# RGB_light_master.net
KiCad netlist of a schematic drawn in EasyEDA Pro
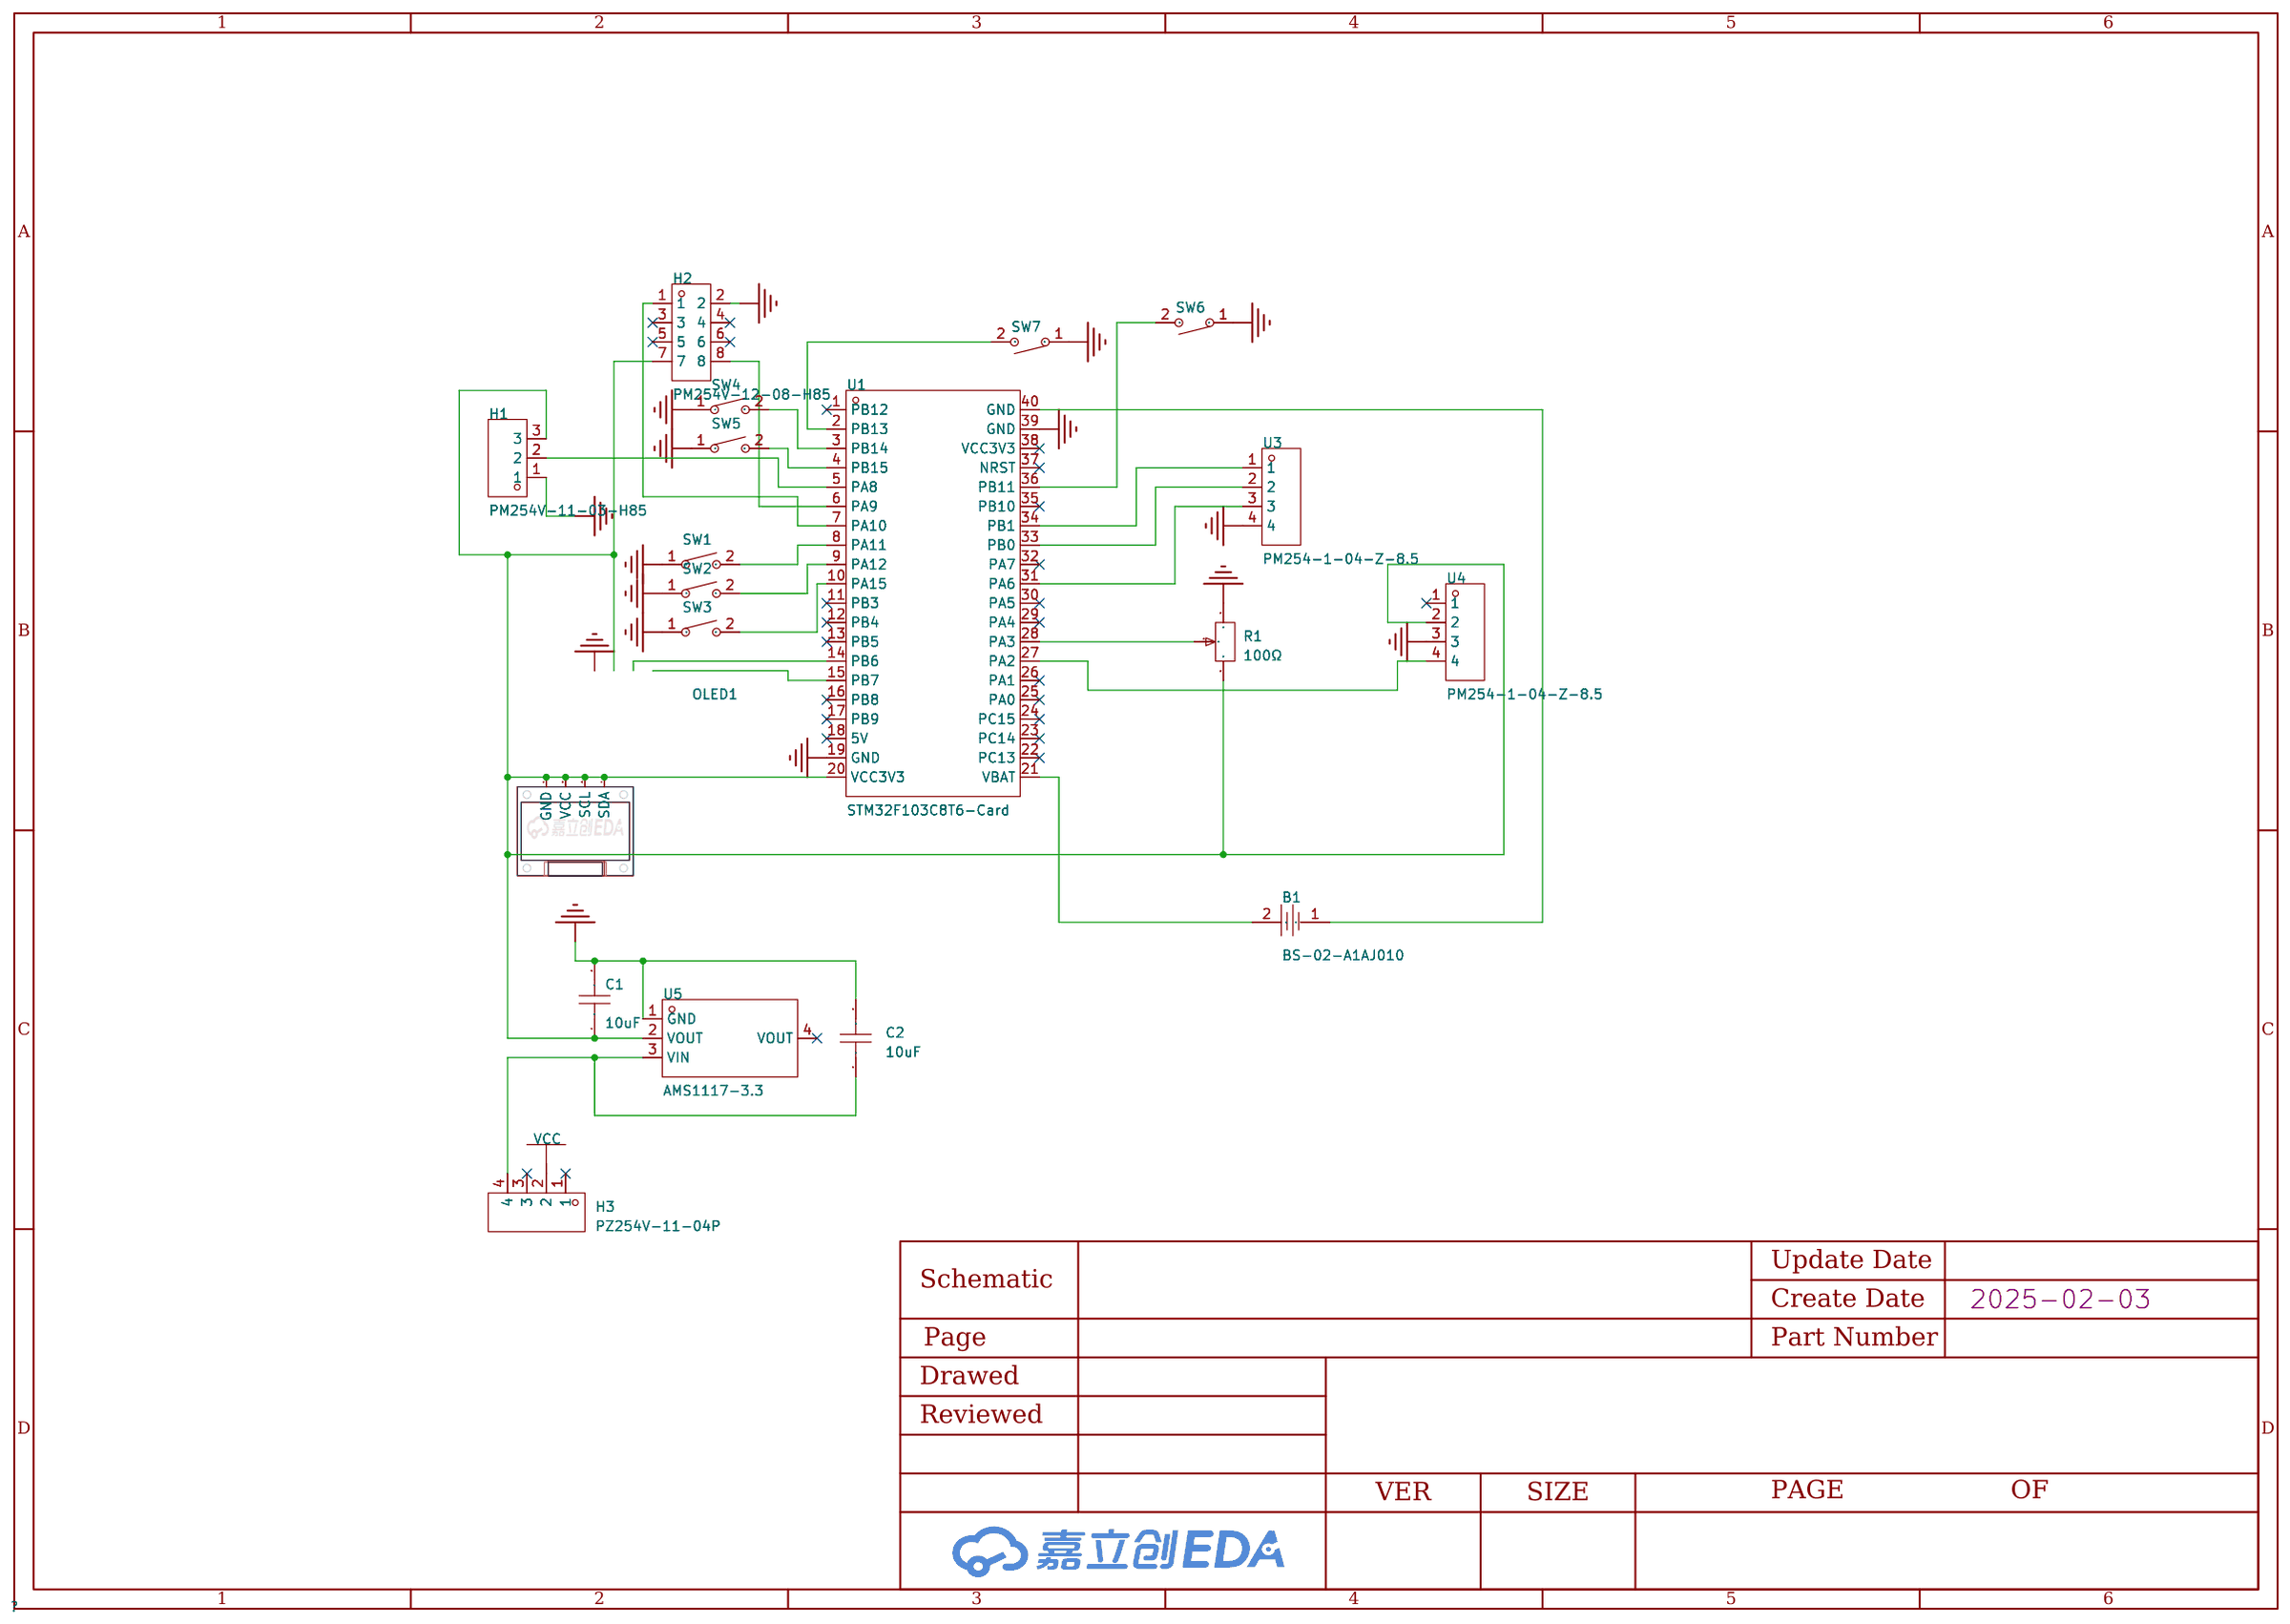
[diagram p0: schematic sheet]

(export (version "E")
  (design (tool "Eeschema 10.0.6"))
  (components
    (comp (ref "B1")
      (value "BS-02-A1AJ010")
      (footprint "easyedapro:BAT-TH_BS-02-A1AJ010")
      (description "连接器类型:电池底座;适用电池规格:CR2032;触头材质:磷青铜;触点电镀:镍;工作温度范围:-25°C~+85°C;")
      (fields (field (name "Manufacturer") "MYOUNG(美阳)"))
      (libsource (lib "easyedapro") (part "BS-02-A1AJ010"))
    )
    (comp (ref "C1")
      (value "10uF")
      (footprint "easyedapro:C0805")
      (description "容值:10uF;精度:±10%;额定电压:25V;材质(温度系数):X5R;")
      (fields
        (field (name "Manufacturer Part") "TMK212BBJ106KGHT")
        (field (name "Manufacturer") "TAIYO YUDEN(太诱)")
      )
      (libsource (lib "easyedapro") (part "TMK212BBJ106KGHT"))
    )
    (comp (ref "C2")
      (value "10uF")
      (footprint "easyedapro:C0805")
      (description "容值:10uF;精度:±10%;额定电压:25V;材质(温度系数):X5R;")
      (fields
        (field (name "Manufacturer Part") "TMK212BBJ106KGHT")
        (field (name "Manufacturer") "TAIYO YUDEN(太诱)")
      )
      (libsource (lib "easyedapro") (part "TMK212BBJ106KGHT"))
    )
    (comp (ref "H1")
      (value "PM254V-11-03-H85")
      (footprint "easyedapro:HDR-TH_3P-P2.54-V-F")
      (description "插孔结构:1x3P;间距:2.54mm;行距:-;安装类型:直插;排数:单排;总孔位数:3P;塑高:-;触头材质:黄铜;触头镀层:-;")
      (fields (field (name "Manufacturer") "XFCN(兴飞)"))
      (libsource (lib "easyedapro") (part "PM254V-11-03-H85"))
    )
    (comp (ref "H2")
      (value "PM254V-12-08-H85")
      (footprint "easyedapro:HDR-TH_8P-P2.54-V-F-R2-C4-S2.54")
      (fields (field (name "Manufacturer") "XFCN(兴飞)"))
      (libsource (lib "easyedapro") (part "PM254V-12-08-H85_C2834799"))
    )
    (comp (ref "H3")
      (value "PZ254V-11-04P")
      (footprint "easyedapro:HDR-TH_4P-P2.54-V-M")
      (fields (field (name "Manufacturer") "XFCN(兴飞)"))
      (libsource (lib "easyedapro") (part "PZ254V-11-04P_C2691448"))
    )
    (comp (ref "OLED1")
      (value "~")
      (footprint "easyedapro:0.96OLED_4P")
      (libsource (lib "easyedapro") (part "0.96OLED模块_4P"))
    )
    (comp (ref "R1")
      (value "100Ω")
      (footprint "easyedapro:RES-ADJ-TH_3296W")
      (description "阻值:100Ω;精度:±10%;")
      (fields (field (name "Manufacturer Part") "3296W-1-101LF") (field (name "Manufacturer") "BOURNS"))
      (libsource (lib "easyedapro") (part "3296W-1-101LF"))
    )
    (comp (ref "SW1")
      (value "TC-1101T-C-B-B")
      (footprint "easyedapro:KEY-TH_2P-L6.0-W3.5-P6.50")
      (fields (field (name "Manufacturer") "XKB Connectivity(中国星坤)"))
      (libsource (lib "easyedapro") (part "TC-1101T-C-B-B"))
    )
    (comp (ref "SW2")
      (value "TC-1101T-C-B-B")
      (footprint "easyedapro:KEY-TH_2P-L6.0-W3.5-P6.50")
      (fields (field (name "Manufacturer") "XKB Connectivity(中国星坤)"))
      (libsource (lib "easyedapro") (part "TC-1101T-C-B-B"))
    )
    (comp (ref "SW3")
      (value "TC-1101T-C-B-B")
      (footprint "easyedapro:KEY-TH_2P-L6.0-W3.5-P6.50")
      (fields (field (name "Manufacturer") "XKB Connectivity(中国星坤)"))
      (libsource (lib "easyedapro") (part "TC-1101T-C-B-B"))
    )
    (comp (ref "SW4")
      (value "TC-1101T-C-B-B")
      (footprint "easyedapro:KEY-TH_2P-L6.0-W3.5-P6.50")
      (fields (field (name "Manufacturer") "XKB Connectivity(中国星坤)"))
      (libsource (lib "easyedapro") (part "TC-1101T-C-B-B"))
    )
    (comp (ref "SW5")
      (value "TC-1101T-C-B-B")
      (footprint "easyedapro:KEY-TH_2P-L6.0-W3.5-P6.50")
      (fields (field (name "Manufacturer") "XKB Connectivity(中国星坤)"))
      (libsource (lib "easyedapro") (part "TC-1101T-C-B-B"))
    )
    (comp (ref "SW6")
      (value "TC-1101T-C-B-B")
      (footprint "easyedapro:KEY-TH_2P-L6.0-W3.5-P6.50")
      (fields (field (name "Manufacturer") "XKB Connectivity(中国星坤)"))
      (libsource (lib "easyedapro") (part "TC-1101T-C-B-B"))
    )
    (comp (ref "SW7")
      (value "TC-1101T-C-B-B")
      (footprint "easyedapro:KEY-TH_2P-L6.0-W3.5-P6.50")
      (fields (field (name "Manufacturer") "XKB Connectivity(中国星坤)"))
      (libsource (lib "easyedapro") (part "TC-1101T-C-B-B"))
    )
    (comp (ref "U1")
      (value "STM32F103C8T6-Card")
      (footprint "easyedapro:CONN-TH_L53.3-W22.9_STM32F103C8T6-CARD")
      (libsource (lib "easyedapro") (part "STM32F103C8T6-CARD"))
    )
    (comp (ref "U3")
      (value "PM254-1-04-Z-8.5")
      (footprint "easyedapro:hdr-th_4p-p2.54-v-f")
      (fields (field (name "Manufacturer") "HCTL(华灿天禄)"))
      (libsource (lib "easyedapro") (part "PM254-1-04-Z-8.5"))
    )
    (comp (ref "U4")
      (value "PM254-1-04-Z-8.5")
      (footprint "easyedapro:hdr-th_4p-p2.54-v-f")
      (fields (field (name "Manufacturer") "HCTL(华灿天禄)"))
      (libsource (lib "easyedapro") (part "PM254-1-04-Z-8.5"))
    )
    (comp (ref "U5")
      (value "AMS1117-3.3")
      (footprint "easyedapro:SOT-223-3_L6.5-W3.4-P2.30-LS7.0-BR")
      (description "输出类型:固定;最大输入电压:-;输出电压:3.3V;最大输出电流:1A;电源纹波抑制比(PSRR):72dB@(120Hz);输出极性:正极;")
      (fields (field (name "Manufacturer") "AMS"))
      (libsource (lib "easyedapro") (part "AMS1117-3.3"))
    )
  )
  (nets
    (net (code "1") (name "GND") (class "Default")
      (node (ref "C1") (pin "2") (pinfunction "2_2") (pintype "input"))
      (node (ref "C2") (pin "2") (pinfunction "2_2") (pintype "input"))
      (node (ref "H1") (pin "1") (pinfunction "1_1") (pintype "unspecified"))
      (node (ref "H2") (pin "2") (pinfunction "2_2") (pintype "unspecified"))
      (node (ref "R1") (pin "1") (pinfunction "1_1") (pintype "input"))
      (node (ref "SW1") (pin "1") (pinfunction "1_1") (pintype "unspecified"))
      (node (ref "SW2") (pin "1") (pinfunction "1_1") (pintype "unspecified"))
      (node (ref "SW3") (pin "1") (pinfunction "1_1") (pintype "unspecified"))
      (node (ref "SW4") (pin "1") (pinfunction "1_1") (pintype "unspecified"))
      (node (ref "SW5") (pin "1") (pinfunction "1_1") (pintype "unspecified"))
      (node (ref "SW6") (pin "1") (pinfunction "1_1") (pintype "unspecified"))
      (node (ref "SW7") (pin "1") (pinfunction "1_1") (pintype "unspecified"))
      (node (ref "U1") (pin "19") (pinfunction "GND_19") (pintype "unspecified"))
      (node (ref "U1") (pin "39") (pinfunction "GND_39") (pintype "unspecified"))
      (node (ref "U3") (pin "4") (pinfunction "4_4") (pintype "unspecified"))
      (node (ref "U4") (pin "3") (pinfunction "3_3") (pintype "unspecified"))
      (node (ref "U5") (pin "1") (pinfunction "GND_1") (pintype "unspecified"))
    )
    (net (code "2") (name "Net-(B1-Pad1)") (class "Default")
      (node (ref "B1") (pin "1") (pinfunction "1_1") (pintype "input"))
      (node (ref "U1") (pin "40") (pinfunction "GND_40") (pintype "unspecified"))
    )
    (net (code "3") (name "Net-(OLED1-GND)") (class "Default")
      (node (ref "C1") (pin "1") (pinfunction "1_1") (pintype "input"))
      (node (ref "H1") (pin "3") (pinfunction "3_3") (pintype "unspecified"))
      (node (ref "H2") (pin "7") (pinfunction "7_7") (pintype "unspecified"))
      (node (ref "OLED1") (pin "1") (pinfunction "GND_1") (pintype "input"))
      (node (ref "OLED1") (pin "2") (pinfunction "VCC_2") (pintype "input"))
      (node (ref "OLED1") (pin "3") (pinfunction "SCL_3") (pintype "input"))
      (node (ref "OLED1") (pin "4") (pinfunction "SDA_4") (pintype "input"))
      (node (ref "R1") (pin "3") (pinfunction "3_3") (pintype "input"))
      (node (ref "U1") (pin "20") (pinfunction "VCC3V3_20") (pintype "unspecified"))
      (node (ref "U4") (pin "2") (pinfunction "2_2") (pintype "unspecified"))
      (node (ref "U5") (pin "2") (pinfunction "VOUT_2") (pintype "unspecified"))
    )
    (net (code "4") (name "Net-(U1-PA2)") (class "Default")
      (node (ref "U1") (pin "27") (pinfunction "PA2_27") (pintype "unspecified"))
      (node (ref "U4") (pin "4") (pinfunction "4_4") (pintype "unspecified"))
    )
    (net (code "5") (name "Net-(U1-PA3)") (class "Default")
      (node (ref "R1") (pin "2") (pinfunction "2_2") (pintype "input"))
      (node (ref "U1") (pin "28") (pinfunction "PA3_28") (pintype "unspecified"))
    )
    (net (code "6") (name "Net-(U1-PA6)") (class "Default")
      (node (ref "U1") (pin "31") (pinfunction "PA6_31") (pintype "unspecified"))
      (node (ref "U3") (pin "3") (pinfunction "3_3") (pintype "unspecified"))
    )
    (net (code "7") (name "Net-(U1-PA8)") (class "Default")
      (node (ref "H1") (pin "2") (pinfunction "2_2") (pintype "unspecified"))
      (node (ref "U1") (pin "5") (pinfunction "PA8_5") (pintype "unspecified"))
    )
    (net (code "8") (name "Net-(U1-PA9)") (class "Default")
      (node (ref "H2") (pin "8") (pinfunction "8_8") (pintype "unspecified"))
      (node (ref "U1") (pin "6") (pinfunction "PA9_6") (pintype "unspecified"))
    )
    (net (code "9") (name "Net-(U1-PA10)") (class "Default")
      (node (ref "H2") (pin "1") (pinfunction "1_1") (pintype "unspecified"))
      (node (ref "U1") (pin "7") (pinfunction "PA10_7") (pintype "unspecified"))
    )
    (net (code "10") (name "Net-(U1-PA11)") (class "Default")
      (node (ref "SW1") (pin "2") (pinfunction "2_2") (pintype "unspecified"))
      (node (ref "U1") (pin "8") (pinfunction "PA11_8") (pintype "unspecified"))
    )
    (net (code "11") (name "Net-(U1-PA12)") (class "Default")
      (node (ref "SW2") (pin "2") (pinfunction "2_2") (pintype "unspecified"))
      (node (ref "U1") (pin "9") (pinfunction "PA12_9") (pintype "unspecified"))
    )
    (net (code "12") (name "Net-(U1-PA15)") (class "Default")
      (node (ref "SW3") (pin "2") (pinfunction "2_2") (pintype "unspecified"))
      (node (ref "U1") (pin "10") (pinfunction "PA15_10") (pintype "unspecified"))
    )
    (net (code "13") (name "Net-(U1-PB0)") (class "Default")
      (node (ref "U1") (pin "33") (pinfunction "PB0_33") (pintype "unspecified"))
      (node (ref "U3") (pin "2") (pinfunction "2_2") (pintype "unspecified"))
    )
    (net (code "14") (name "Net-(U1-PB1)") (class "Default")
      (node (ref "U1") (pin "34") (pinfunction "PB1_34") (pintype "unspecified"))
      (node (ref "U3") (pin "1") (pinfunction "1_1") (pintype "unspecified"))
    )
    (net (code "15") (name "Net-(U1-PB11)") (class "Default")
      (node (ref "SW6") (pin "2") (pinfunction "2_2") (pintype "unspecified"))
      (node (ref "U1") (pin "36") (pinfunction "PB11_36") (pintype "unspecified"))
    )
    (net (code "16") (name "Net-(U1-PB13)") (class "Default")
      (node (ref "SW7") (pin "2") (pinfunction "2_2") (pintype "unspecified"))
      (node (ref "U1") (pin "2") (pinfunction "PB13_2") (pintype "unspecified"))
    )
    (net (code "17") (name "Net-(U1-PB14)") (class "Default")
      (node (ref "SW4") (pin "2") (pinfunction "2_2") (pintype "unspecified"))
      (node (ref "U1") (pin "3") (pinfunction "PB14_3") (pintype "unspecified"))
    )
    (net (code "18") (name "Net-(U1-PB15)") (class "Default")
      (node (ref "SW5") (pin "2") (pinfunction "2_2") (pintype "unspecified"))
      (node (ref "U1") (pin "4") (pinfunction "PB15_4") (pintype "unspecified"))
    )
    (net (code "19") (name "Net-(U1-VBAT)") (class "Default")
      (node (ref "B1") (pin "2") (pinfunction "2_2") (pintype "input"))
      (node (ref "U1") (pin "21") (pinfunction "VBAT_21") (pintype "unspecified"))
    )
    (net (code "20") (name "Net-(U5-VIN)") (class "Default")
      (node (ref "C2") (pin "1") (pinfunction "1_1") (pintype "input"))
      (node (ref "H3") (pin "4") (pinfunction "4_4") (pintype "unspecified"))
      (node (ref "U5") (pin "3") (pinfunction "VIN_3") (pintype "unspecified"))
    )
    (net (code "21") (name "VCC") (class "Default")
      (node (ref "H3") (pin "2") (pinfunction "2_2") (pintype "unspecified"))
    )
    (net (code "22") (name "unconnected-(H2-Pad3)") (class "Default")
      (node (ref "H2") (pin "3") (pinfunction "3_3") (pintype "unspecified+no_connect"))
    )
    (net (code "23") (name "unconnected-(H2-Pad4)") (class "Default")
      (node (ref "H2") (pin "4") (pinfunction "4_4") (pintype "unspecified+no_connect"))
    )
    (net (code "24") (name "unconnected-(H2-Pad5)") (class "Default")
      (node (ref "H2") (pin "5") (pinfunction "5_5") (pintype "unspecified+no_connect"))
    )
    (net (code "25") (name "unconnected-(H2-Pad6)") (class "Default")
      (node (ref "H2") (pin "6") (pinfunction "6_6") (pintype "unspecified+no_connect"))
    )
    (net (code "26") (name "unconnected-(H3-Pad1)") (class "Default")
      (node (ref "H3") (pin "1") (pinfunction "1_1") (pintype "unspecified+no_connect"))
    )
    (net (code "27") (name "unconnected-(H3-Pad3)") (class "Default")
      (node (ref "H3") (pin "3") (pinfunction "3_3") (pintype "unspecified+no_connect"))
    )
    (net (code "28") (name "unconnected-(U1-5V-Pad18)") (class "Default")
      (node (ref "U1") (pin "18") (pinfunction "5V_18") (pintype "unspecified+no_connect"))
    )
    (net (code "29") (name "unconnected-(U1-NRST-Pad37)") (class "Default")
      (node (ref "U1") (pin "37") (pinfunction "NRST_37") (pintype "unspecified+no_connect"))
    )
    (net (code "30") (name "unconnected-(U1-PA0-Pad25)") (class "Default")
      (node (ref "U1") (pin "25") (pinfunction "PA0_25") (pintype "unspecified+no_connect"))
    )
    (net (code "31") (name "unconnected-(U1-PA1-Pad26)") (class "Default")
      (node (ref "U1") (pin "26") (pinfunction "PA1_26") (pintype "unspecified+no_connect"))
    )
    (net (code "32") (name "unconnected-(U1-PA4-Pad29)") (class "Default")
      (node (ref "U1") (pin "29") (pinfunction "PA4_29") (pintype "unspecified+no_connect"))
    )
    (net (code "33") (name "unconnected-(U1-PA5-Pad30)") (class "Default")
      (node (ref "U1") (pin "30") (pinfunction "PA5_30") (pintype "unspecified+no_connect"))
    )
    (net (code "34") (name "unconnected-(U1-PA7-Pad32)") (class "Default")
      (node (ref "U1") (pin "32") (pinfunction "PA7_32") (pintype "unspecified+no_connect"))
    )
    (net (code "35") (name "unconnected-(U1-PB3-Pad11)") (class "Default")
      (node (ref "U1") (pin "11") (pinfunction "PB3_11") (pintype "unspecified+no_connect"))
    )
    (net (code "36") (name "unconnected-(U1-PB4-Pad12)") (class "Default")
      (node (ref "U1") (pin "12") (pinfunction "PB4_12") (pintype "unspecified+no_connect"))
    )
    (net (code "37") (name "unconnected-(U1-PB5-Pad13)") (class "Default")
      (node (ref "U1") (pin "13") (pinfunction "PB5_13") (pintype "unspecified+no_connect"))
    )
    (net (code "38") (name "unconnected-(U1-PB6-Pad14)") (class "Default")
      (node (ref "U1") (pin "14") (pinfunction "PB6_14") (pintype "unspecified"))
    )
    (net (code "39") (name "unconnected-(U1-PB7-Pad15)") (class "Default")
      (node (ref "U1") (pin "15") (pinfunction "PB7_15") (pintype "unspecified"))
    )
    (net (code "40") (name "unconnected-(U1-PB8-Pad16)") (class "Default")
      (node (ref "U1") (pin "16") (pinfunction "PB8_16") (pintype "unspecified+no_connect"))
    )
    (net (code "41") (name "unconnected-(U1-PB9-Pad17)") (class "Default")
      (node (ref "U1") (pin "17") (pinfunction "PB9_17") (pintype "unspecified+no_connect"))
    )
    (net (code "42") (name "unconnected-(U1-PB10-Pad35)") (class "Default")
      (node (ref "U1") (pin "35") (pinfunction "PB10_35") (pintype "unspecified+no_connect"))
    )
    (net (code "43") (name "unconnected-(U1-PB12-Pad1)") (class "Default")
      (node (ref "U1") (pin "1") (pinfunction "PB12_1") (pintype "unspecified+no_connect"))
    )
    (net (code "44") (name "unconnected-(U1-PC13-Pad22)") (class "Default")
      (node (ref "U1") (pin "22") (pinfunction "PC13_22") (pintype "unspecified+no_connect"))
    )
    (net (code "45") (name "unconnected-(U1-PC14-Pad23)") (class "Default")
      (node (ref "U1") (pin "23") (pinfunction "PC14_23") (pintype "unspecified+no_connect"))
    )
    (net (code "46") (name "unconnected-(U1-PC15-Pad24)") (class "Default")
      (node (ref "U1") (pin "24") (pinfunction "PC15_24") (pintype "unspecified+no_connect"))
    )
    (net (code "47") (name "unconnected-(U1-VCC3V3-Pad38)") (class "Default")
      (node (ref "U1") (pin "38") (pinfunction "VCC3V3_38") (pintype "unspecified+no_connect"))
    )
    (net (code "48") (name "unconnected-(U4-Pad1)") (class "Default")
      (node (ref "U4") (pin "1") (pinfunction "1_1") (pintype "unspecified+no_connect"))
    )
    (net (code "49") (name "unconnected-(U5-VOUT-Pad4)") (class "Default")
      (node (ref "U5") (pin "4") (pinfunction "VOUT_4") (pintype "unspecified+no_connect"))
    )
  )
)
